# TG-Watch02A-Flex-v2.net
KiCad netlist of a schematic drawn in EAGLE
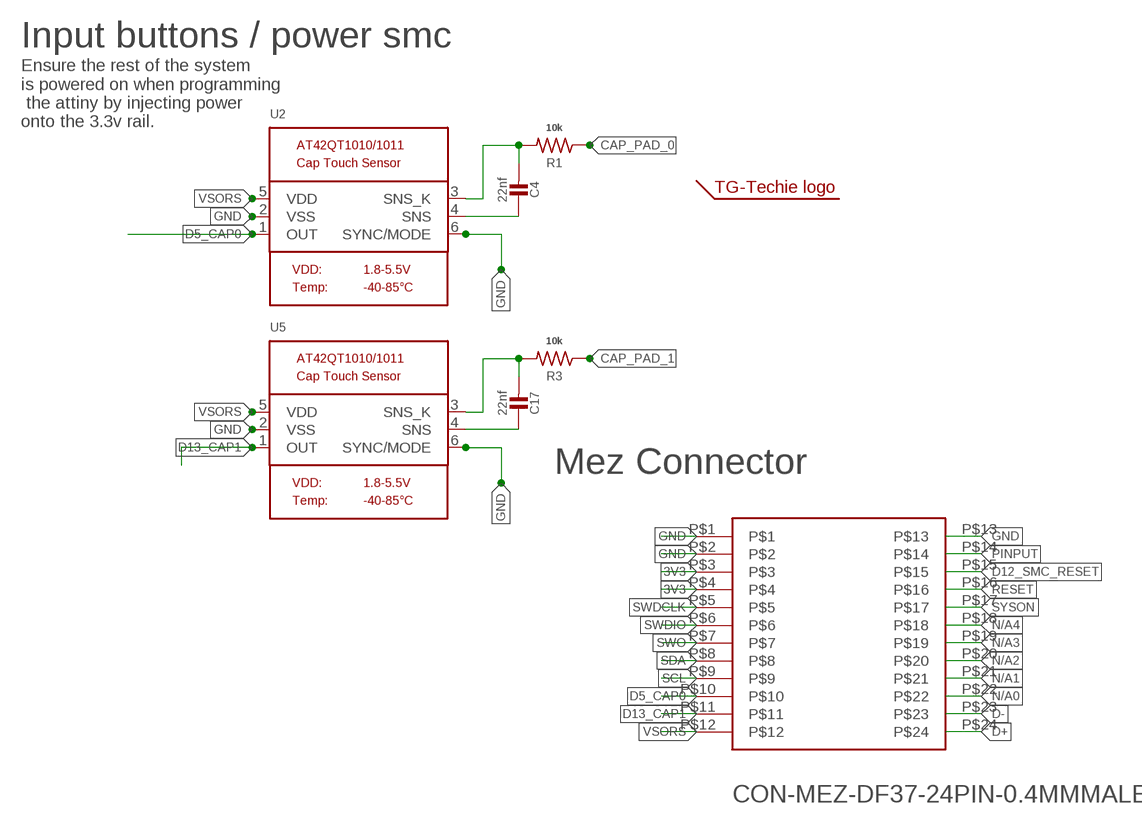
[diagram p0: schematic, sheet 1]

(export (version "E")
  (design (tool "Eeschema 10.0.6"))
  (components
    (comp (ref "C4")
      (value "22nf")
      (footprint "eagle-import:_0402")
      (libsource (lib "eagle-import") (part "CAP_CERAMIC_0402"))
    )
    (comp (ref "C17")
      (value "22nf")
      (footprint "eagle-import:_0402")
      (libsource (lib "eagle-import") (part "CAP_CERAMIC_0402"))
    )
    (comp (ref "R1")
      (value "10k")
      (footprint "eagle-import:TG_0402")
      (libsource (lib "eagle-import") (part "R_TG_0402"))
    )
    (comp (ref "R3")
      (value "10k")
      (footprint "eagle-import:TG_0402")
      (libsource (lib "eagle-import") (part "R_TG_0402"))
    )
    (comp (ref "U$1")
      (value "LOGO-TG-TECHIE2.5MM-SYMB")
      (footprint "eagle-import:TG-LOGO-2.5MM-SYMB")
      (libsource (lib "eagle-import") (part "LOGO-TG-TECHIE2.5MM-SYMB"))
    )
    (comp (ref "U$11")
      (value "CON-MEZ-DF37-24PIN-0.4MMMALE")
      (footprint "eagle-import:MEZ-DF37B-24DP")
      (libsource (lib "eagle-import") (part "CON-MEZ-DF37-24PIN-0.4MMMALE"))
    )
    (comp (ref "U2")
      (value "SEN-CAPTOUCH-AT42QT1010/1")
      (footprint "eagle-import:MICROBUILDER_SOT23-6")
      (libsource (lib "eagle-import") (part "SEN-CAPTOUCH-AT42QT1010/1"))
    )
    (comp (ref "U5")
      (value "SEN-CAPTOUCH-AT42QT1010/1")
      (footprint "eagle-import:MICROBUILDER_SOT23-6")
      (libsource (lib "eagle-import") (part "SEN-CAPTOUCH-AT42QT1010/1"))
    )
  )
  (nets
    (net (code "1") (name "3V3") (class "Default")
      (node (ref "U$11") (pin "P$3") (pinfunction "P$3_P$3") (pintype "bidirectional"))
      (node (ref "U$11") (pin "P$4") (pinfunction "P$4_P$4") (pintype "bidirectional"))
    )
    (net (code "2") (name "CAP_PAD_0") (class "Default")
      (node (ref "R1") (pin "1") (pinfunction "1_1") (pintype "passive"))
    )
    (net (code "3") (name "CAP_PAD_1") (class "Default")
      (node (ref "R3") (pin "1") (pinfunction "1_1") (pintype "passive"))
    )
    (net (code "4") (name "D+") (class "Default")
      (node (ref "U$11") (pin "P$24") (pinfunction "P$24_P$24") (pintype "bidirectional"))
    )
    (net (code "5") (name "D-") (class "Default")
      (node (ref "U$11") (pin "P$23") (pinfunction "P$23_P$23") (pintype "bidirectional"))
    )
    (net (code "6") (name "D5_CAP0") (class "Default")
      (node (ref "U$11") (pin "P$10") (pinfunction "P$10_P$10") (pintype "bidirectional"))
      (node (ref "U2") (pin "1") (pinfunction "OUT_1") (pintype "output"))
    )
    (net (code "7") (name "D12_SMC_RESET") (class "Default")
      (node (ref "U$11") (pin "P$15") (pinfunction "P$15_P$15") (pintype "bidirectional"))
    )
    (net (code "8") (name "D13_CAP1") (class "Default")
      (node (ref "U$11") (pin "P$11") (pinfunction "P$11_P$11") (pintype "bidirectional"))
      (node (ref "U5") (pin "1") (pinfunction "OUT_1") (pintype "output"))
    )
    (net (code "9") (name "GND") (class "Default")
      (node (ref "U$11") (pin "P$1") (pinfunction "P$1_P$1") (pintype "bidirectional"))
      (node (ref "U$11") (pin "P$13") (pinfunction "P$13_P$13") (pintype "bidirectional"))
      (node (ref "U$11") (pin "P$2") (pinfunction "P$2_P$2") (pintype "bidirectional"))
      (node (ref "U2") (pin "2") (pinfunction "VSS_2") (pintype "power_in"))
      (node (ref "U2") (pin "6") (pinfunction "SYNC/MODE_6") (pintype "input"))
      (node (ref "U5") (pin "2") (pinfunction "VSS_2") (pintype "power_in"))
      (node (ref "U5") (pin "6") (pinfunction "SYNC/MODE_6") (pintype "input"))
    )
    (net (code "10") (name "Net-(U2-SNS)") (class "Default")
      (node (ref "C4") (pin "1") (pinfunction "1_1") (pintype "passive"))
      (node (ref "U2") (pin "4") (pinfunction "SNS_4") (pintype "bidirectional"))
    )
    (net (code "11") (name "Net-(U2-SNS_K)") (class "Default")
      (node (ref "C4") (pin "2") (pinfunction "2_2") (pintype "passive"))
      (node (ref "R1") (pin "2") (pinfunction "2_2") (pintype "passive"))
      (node (ref "U2") (pin "3") (pinfunction "SNS_K_3") (pintype "bidirectional"))
    )
    (net (code "12") (name "Net-(U5-SNS)") (class "Default")
      (node (ref "C17") (pin "1") (pinfunction "1_1") (pintype "passive"))
      (node (ref "U5") (pin "4") (pinfunction "SNS_4") (pintype "bidirectional"))
    )
    (net (code "13") (name "Net-(U5-SNS_K)") (class "Default")
      (node (ref "C17") (pin "2") (pinfunction "2_2") (pintype "passive"))
      (node (ref "R3") (pin "2") (pinfunction "2_2") (pintype "passive"))
      (node (ref "U5") (pin "3") (pinfunction "SNS_K_3") (pintype "bidirectional"))
    )
    (net (code "14") (name "N{slash}A0") (class "Default")
      (node (ref "U$11") (pin "P$22") (pinfunction "P$22_P$22") (pintype "bidirectional"))
    )
    (net (code "15") (name "N{slash}A1") (class "Default")
      (node (ref "U$11") (pin "P$21") (pinfunction "P$21_P$21") (pintype "bidirectional"))
    )
    (net (code "16") (name "N{slash}A2") (class "Default")
      (node (ref "U$11") (pin "P$20") (pinfunction "P$20_P$20") (pintype "bidirectional"))
    )
    (net (code "17") (name "N{slash}A3") (class "Default")
      (node (ref "U$11") (pin "P$19") (pinfunction "P$19_P$19") (pintype "bidirectional"))
    )
    (net (code "18") (name "N{slash}A4") (class "Default")
      (node (ref "U$11") (pin "P$18") (pinfunction "P$18_P$18") (pintype "bidirectional"))
    )
    (net (code "19") (name "PINPUT") (class "Default")
      (node (ref "U$11") (pin "P$14") (pinfunction "P$14_P$14") (pintype "bidirectional"))
    )
    (net (code "20") (name "RESET") (class "Default")
      (node (ref "U$11") (pin "P$16") (pinfunction "P$16_P$16") (pintype "bidirectional"))
    )
    (net (code "21") (name "SCL") (class "Default")
      (node (ref "U$11") (pin "P$9") (pinfunction "P$9_P$9") (pintype "bidirectional"))
    )
    (net (code "22") (name "SDA") (class "Default")
      (node (ref "U$11") (pin "P$8") (pinfunction "P$8_P$8") (pintype "bidirectional"))
    )
    (net (code "23") (name "SWDCLK") (class "Default")
      (node (ref "U$11") (pin "P$5") (pinfunction "P$5_P$5") (pintype "bidirectional"))
    )
    (net (code "24") (name "SWDIO") (class "Default")
      (node (ref "U$11") (pin "P$6") (pinfunction "P$6_P$6") (pintype "bidirectional"))
    )
    (net (code "25") (name "SWO") (class "Default")
      (node (ref "U$11") (pin "P$7") (pinfunction "P$7_P$7") (pintype "bidirectional"))
    )
    (net (code "26") (name "SYSON") (class "Default")
      (node (ref "U$11") (pin "P$17") (pinfunction "P$17_P$17") (pintype "bidirectional"))
    )
    (net (code "27") (name "VSORS") (class "Default")
      (node (ref "U$11") (pin "P$12") (pinfunction "P$12_P$12") (pintype "bidirectional"))
      (node (ref "U2") (pin "5") (pinfunction "VDD_5") (pintype "power_in"))
      (node (ref "U5") (pin "5") (pinfunction "VDD_5") (pintype "power_in"))
    )
  )
)
